# 0402-tight-term.net
KiCad netlist of a schematic drawn in EAGLE
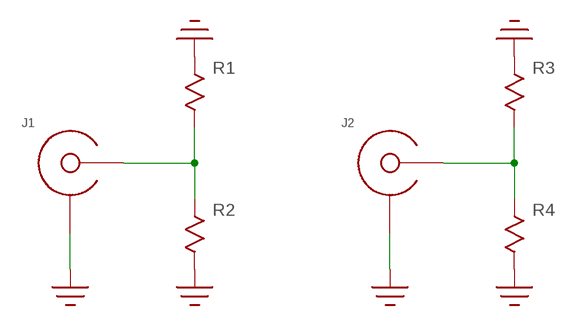
[diagram p0: schematic, sheet 1]

(export (version "E")
  (design (tool "Eeschema 10.0.6"))
  (components
    (comp (ref "J1")
      (value "SMA-EDGE-LAUNCH4020_TAPER")
      (footprint "eagle-import:SMA_EDGE_LAUNCH_2L_4020_TAPER")
      (libsource (lib "eagle-import") (part "SMA-EDGE-LAUNCH4020_TAPER"))
    )
    (comp (ref "J2")
      (value "SMA-EDGE-LAUNCH4020_TAPER")
      (footprint "eagle-import:SMA_EDGE_LAUNCH_2L_4020_TAPER")
      (libsource (lib "eagle-import") (part "SMA-EDGE-LAUNCH4020_TAPER"))
    )
    (comp (ref "R1")
      (value "R0402-TIGHT")
      (footprint "eagle-import:0402-TIGHT")
      (libsource (lib "eagle-import") (part "R0402-TIGHT"))
    )
    (comp (ref "R2")
      (value "R0402-TIGHT")
      (footprint "eagle-import:0402-TIGHT")
      (libsource (lib "eagle-import") (part "R0402-TIGHT"))
    )
    (comp (ref "R3")
      (value "R0402")
      (footprint "eagle-import:0402")
      (libsource (lib "eagle-import") (part "R0402"))
    )
    (comp (ref "R4")
      (value "R0402")
      (footprint "eagle-import:0402")
      (libsource (lib "eagle-import") (part "R0402"))
    )
  )
  (nets
    (net (code "1") (name "GND") (class "Default")
      (node (ref "J1") (pin "BOTTOM_GND") (pinfunction "SHIELD_BOTTOM_GND") (pintype "bidirectional"))
      (node (ref "J1") (pin "GND@1") (pinfunction "SHIELD_GND@1") (pintype "bidirectional"))
      (node (ref "J1") (pin "GND@14") (pinfunction "SHIELD_GND@14") (pintype "bidirectional"))
      (node (ref "J1") (pin "GND@15") (pinfunction "SHIELD_GND@15") (pintype "bidirectional"))
      (node (ref "J1") (pin "GND@16") (pinfunction "SHIELD_GND@16") (pintype "bidirectional"))
      (node (ref "J1") (pin "GND@17") (pinfunction "SHIELD_GND@17") (pintype "bidirectional"))
      (node (ref "J1") (pin "GND@2") (pinfunction "SHIELD_GND@2") (pintype "bidirectional"))
      (node (ref "J1") (pin "GND@3") (pinfunction "SHIELD_GND@3") (pintype "bidirectional"))
      (node (ref "J1") (pin "GND@4") (pinfunction "SHIELD_GND@4") (pintype "bidirectional"))
      (node (ref "J1") (pin "GND@5") (pinfunction "SHIELD_GND@5") (pintype "bidirectional"))
      (node (ref "J1") (pin "GND@6") (pinfunction "SHIELD_GND@6") (pintype "bidirectional"))
      (node (ref "J1") (pin "GND@7") (pinfunction "SHIELD_GND@7") (pintype "bidirectional"))
      (node (ref "J1") (pin "GND@8") (pinfunction "SHIELD_GND@8") (pintype "bidirectional"))
      (node (ref "J1") (pin "GND_PAD1") (pinfunction "SHIELD_GND_PAD1") (pintype "bidirectional"))
      (node (ref "J1") (pin "GND_PAD2") (pinfunction "SHIELD_GND_PAD2") (pintype "bidirectional"))
      (node (ref "J1") (pin "P$1") (pinfunction "SHIELD_P$1") (pintype "bidirectional"))
      (node (ref "J1") (pin "P$2") (pinfunction "SHIELD_P$2") (pintype "bidirectional"))
      (node (ref "J2") (pin "BOTTOM_GND") (pinfunction "SHIELD_BOTTOM_GND") (pintype "bidirectional"))
      (node (ref "J2") (pin "GND@1") (pinfunction "SHIELD_GND@1") (pintype "bidirectional"))
      (node (ref "J2") (pin "GND@14") (pinfunction "SHIELD_GND@14") (pintype "bidirectional"))
      (node (ref "J2") (pin "GND@15") (pinfunction "SHIELD_GND@15") (pintype "bidirectional"))
      (node (ref "J2") (pin "GND@16") (pinfunction "SHIELD_GND@16") (pintype "bidirectional"))
      (node (ref "J2") (pin "GND@17") (pinfunction "SHIELD_GND@17") (pintype "bidirectional"))
      (node (ref "J2") (pin "GND@2") (pinfunction "SHIELD_GND@2") (pintype "bidirectional"))
      (node (ref "J2") (pin "GND@3") (pinfunction "SHIELD_GND@3") (pintype "bidirectional"))
      (node (ref "J2") (pin "GND@4") (pinfunction "SHIELD_GND@4") (pintype "bidirectional"))
      (node (ref "J2") (pin "GND@5") (pinfunction "SHIELD_GND@5") (pintype "bidirectional"))
      (node (ref "J2") (pin "GND@6") (pinfunction "SHIELD_GND@6") (pintype "bidirectional"))
      (node (ref "J2") (pin "GND@7") (pinfunction "SHIELD_GND@7") (pintype "bidirectional"))
      (node (ref "J2") (pin "GND@8") (pinfunction "SHIELD_GND@8") (pintype "bidirectional"))
      (node (ref "J2") (pin "GND_PAD1") (pinfunction "SHIELD_GND_PAD1") (pintype "bidirectional"))
      (node (ref "J2") (pin "GND_PAD2") (pinfunction "SHIELD_GND_PAD2") (pintype "bidirectional"))
      (node (ref "J2") (pin "P$1") (pinfunction "SHIELD_P$1") (pintype "bidirectional"))
      (node (ref "J2") (pin "P$2") (pinfunction "SHIELD_P$2") (pintype "bidirectional"))
      (node (ref "R1") (pin "P$1") (pinfunction "P$3_P$1") (pintype "bidirectional"))
      (node (ref "R2") (pin "P$2") (pinfunction "P$4_P$2") (pintype "bidirectional"))
      (node (ref "R3") (pin "1") (pinfunction "P$3_1") (pintype "bidirectional"))
      (node (ref "R4") (pin "2") (pinfunction "P$4_2") (pintype "bidirectional"))
    )
    (net (code "2") (name "Net-(J1-CENTER)") (class "Default")
      (node (ref "J1") (pin "CENTER@1") (pinfunction "CENTER_CENTER@1") (pintype "bidirectional"))
      (node (ref "R1") (pin "P$2") (pinfunction "P$4_P$2") (pintype "bidirectional"))
      (node (ref "R2") (pin "P$1") (pinfunction "P$3_P$1") (pintype "bidirectional"))
    )
    (net (code "3") (name "Net-(J2-CENTER)") (class "Default")
      (node (ref "J2") (pin "CENTER@1") (pinfunction "CENTER_CENTER@1") (pintype "bidirectional"))
      (node (ref "R3") (pin "2") (pinfunction "P$4_2") (pintype "bidirectional"))
      (node (ref "R4") (pin "1") (pinfunction "P$3_1") (pintype "bidirectional"))
    )
  )
)
